# TeamB.net
KiCad netlist of a schematic drawn in EAGLE
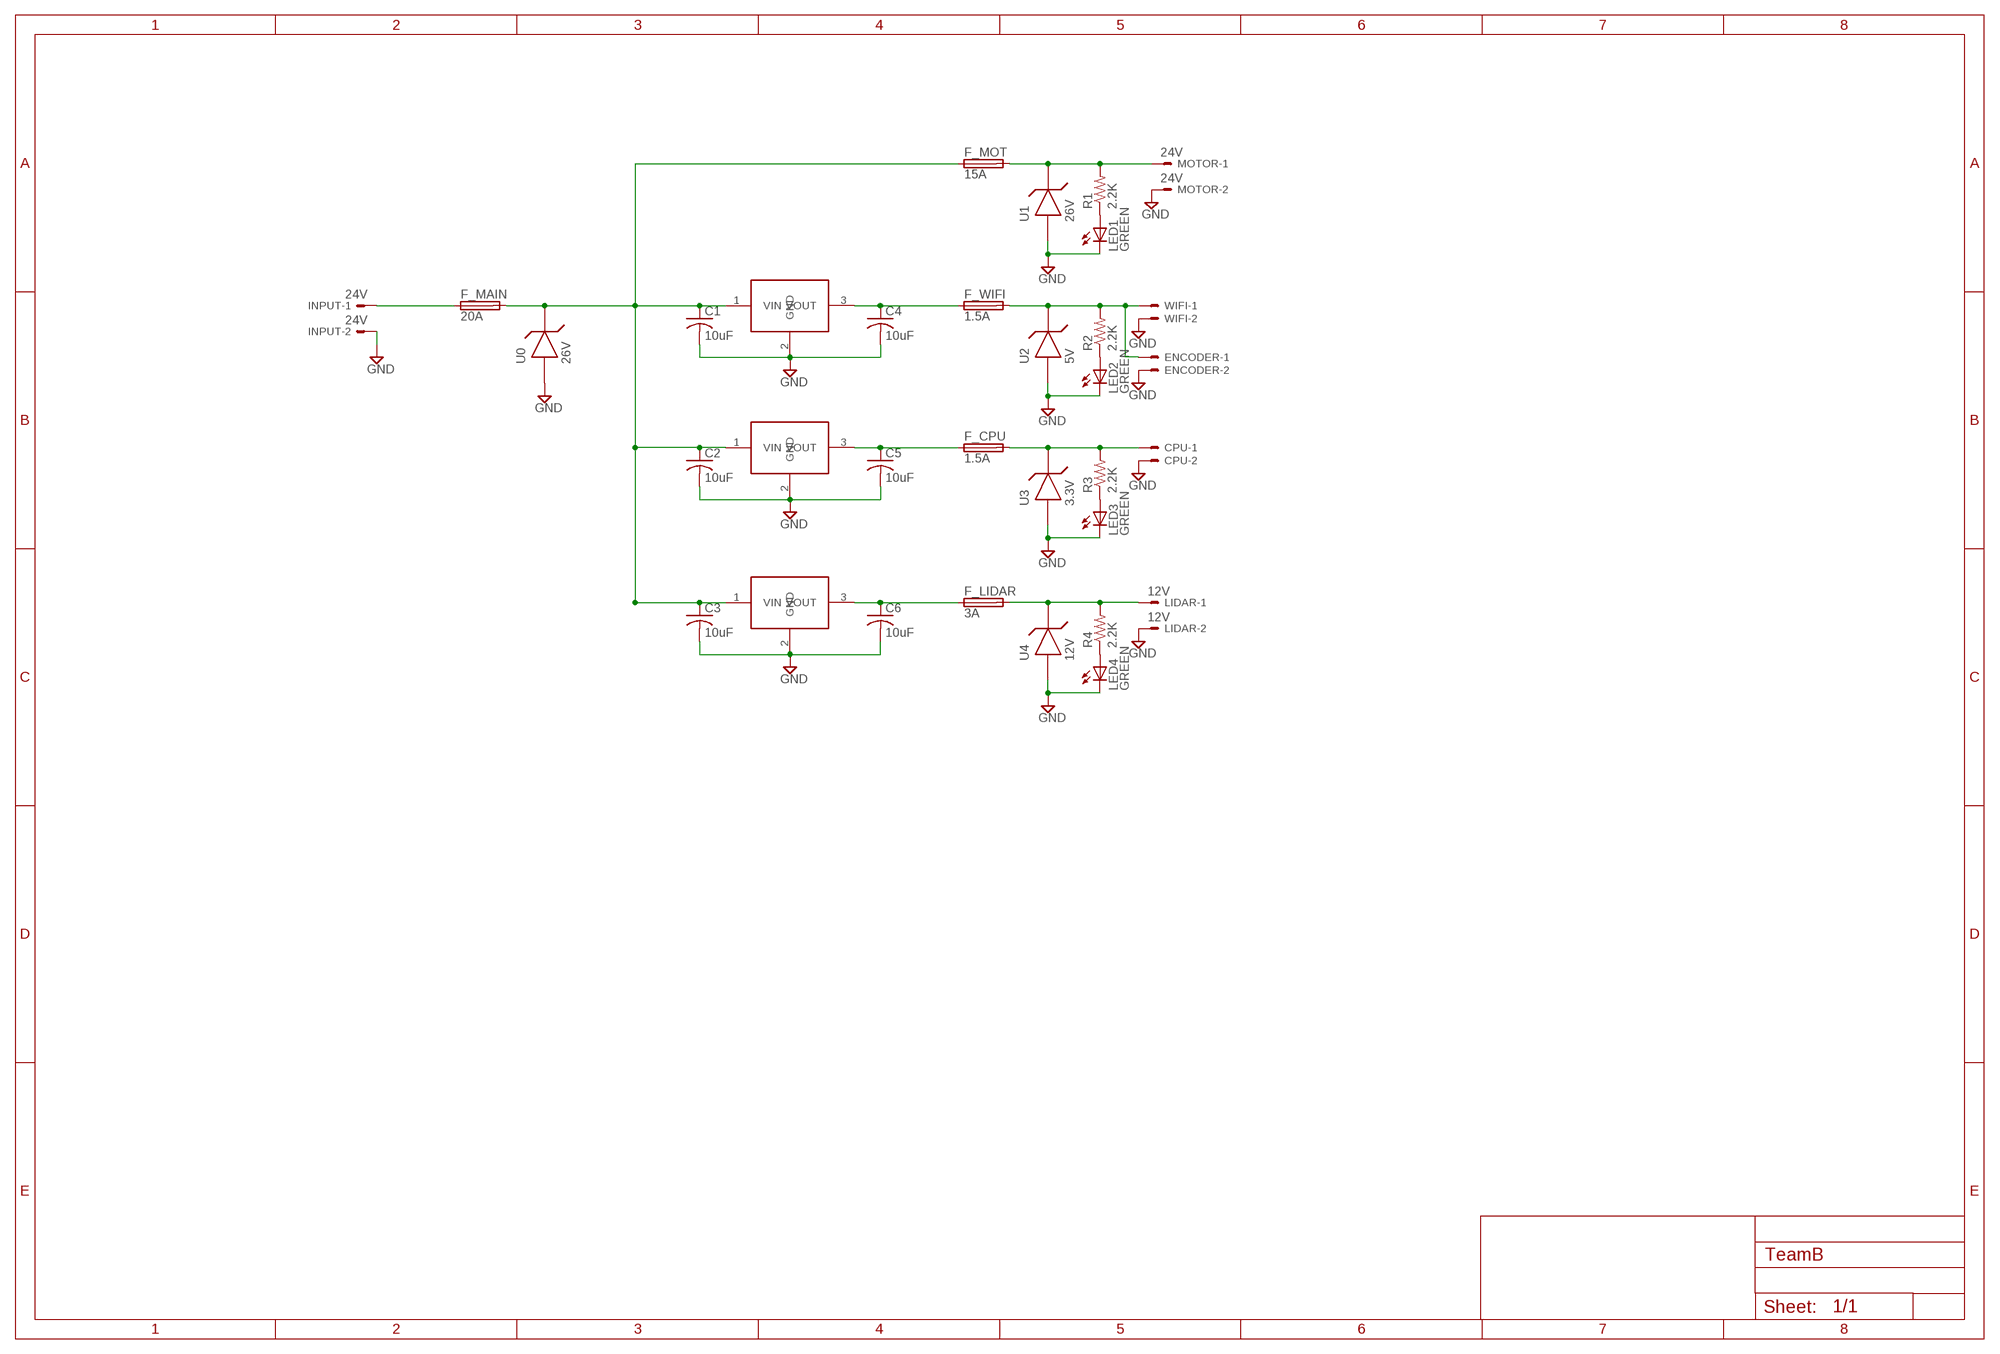
[diagram p0: schematic, sheet 1]

(export (version "E")
  (design (tool "Eeschema 10.0.6"))
  (components
    (comp (ref "C1")
      (value "10uF")
      (footprint "eagle-import:C1206")
      (libsource (lib "eagle-import") (part "C-USC1206"))
    )
    (comp (ref "C2")
      (value "10uF")
      (footprint "eagle-import:C1206")
      (libsource (lib "eagle-import") (part "C-USC1206"))
    )
    (comp (ref "C3")
      (value "10uF")
      (footprint "eagle-import:C1206")
      (libsource (lib "eagle-import") (part "C-USC1206"))
    )
    (comp (ref "C4")
      (value "10uF")
      (footprint "eagle-import:C1206")
      (libsource (lib "eagle-import") (part "C-USC1206"))
    )
    (comp (ref "C5")
      (value "10uF")
      (footprint "eagle-import:C1206")
      (libsource (lib "eagle-import") (part "C-USC1206"))
    )
    (comp (ref "C6")
      (value "10uF")
      (footprint "eagle-import:C1206")
      (libsource (lib "eagle-import") (part "C-USC1206"))
    )
    (comp (ref "CPU")
      (value "3.3V")
      (footprint "eagle-import:70553-02")
      (libsource (lib "eagle-import") (part "C-GRID-02-70553"))
    )
    (comp (ref "ENCODER")
      (value "5V")
      (footprint "eagle-import:70553-02")
      (libsource (lib "eagle-import") (part "C-GRID-02-70553"))
    )
    (comp (ref "F_CPU")
      (value "1.5A")
      (footprint "eagle-import:TE5")
      (libsource (lib "eagle-import") (part "TE5"))
    )
    (comp (ref "F_LIDAR")
      (value "3A")
      (footprint "eagle-import:TE5")
      (libsource (lib "eagle-import") (part "TE5"))
    )
    (comp (ref "F_MAIN")
      (value "20A")
      (footprint "eagle-import:TE5")
      (libsource (lib "eagle-import") (part "TE5"))
    )
    (comp (ref "F_MOT")
      (value "15A")
      (footprint "eagle-import:TE5")
      (libsource (lib "eagle-import") (part "TE5"))
    )
    (comp (ref "F_WIFI")
      (value "1.5A")
      (footprint "eagle-import:TE5")
      (libsource (lib "eagle-import") (part "TE5"))
    )
    (comp (ref "INPUT")
      (value "24V")
      (footprint "eagle-import:5566-2")
      (libsource (lib "eagle-import") (part "5566-2"))
    )
    (comp (ref "LED1")
      (value "GREEN")
      (footprint "eagle-import:SML1206")
      (libsource (lib "eagle-import") (part "LEDSML1206"))
    )
    (comp (ref "LED2")
      (value "GREEN")
      (footprint "eagle-import:SML1206")
      (libsource (lib "eagle-import") (part "LEDSML1206"))
    )
    (comp (ref "LED3")
      (value "GREEN")
      (footprint "eagle-import:SML1206")
      (libsource (lib "eagle-import") (part "LEDSML1206"))
    )
    (comp (ref "LED4")
      (value "GREEN")
      (footprint "eagle-import:SML1206")
      (libsource (lib "eagle-import") (part "LEDSML1206"))
    )
    (comp (ref "LIDAR")
      (value "12V")
      (footprint "eagle-import:5566-2")
      (libsource (lib "eagle-import") (part "5566-2"))
    )
    (comp (ref "MOTOR")
      (value "24V")
      (footprint "eagle-import:5566-2")
      (libsource (lib "eagle-import") (part "5566-2"))
    )
    (comp (ref "Q1")
      (value "MIC29300-5.0WU")
      (footprint "eagle-import:TO220")
      (libsource (lib "eagle-import") (part "MIC29150/29300/29500"))
    )
    (comp (ref "Q2")
      (value "MIC29300-3.3WU")
      (footprint "eagle-import:TO220")
      (libsource (lib "eagle-import") (part "MIC29150/29300/29500"))
    )
    (comp (ref "Q3")
      (value "MIC29300-12WU")
      (footprint "eagle-import:TO220")
      (libsource (lib "eagle-import") (part "MIC29150/29300/29500"))
    )
    (comp (ref "R1")
      (value "2.2K")
      (footprint "eagle-import:R1206")
      (libsource (lib "eagle-import") (part "R-US_R1206"))
    )
    (comp (ref "R2")
      (value "2.2K")
      (footprint "eagle-import:R1206")
      (libsource (lib "eagle-import") (part "R-US_R1206"))
    )
    (comp (ref "R3")
      (value "2.2K")
      (footprint "eagle-import:R1206")
      (libsource (lib "eagle-import") (part "R-US_R1206"))
    )
    (comp (ref "R4")
      (value "2.2K")
      (footprint "eagle-import:R1206")
      (libsource (lib "eagle-import") (part "R-US_R1206"))
    )
    (comp (ref "U0")
      (value "26V")
      (footprint "eagle-import:SMA")
      (libsource (lib "eagle-import") (part "TVS-DIODE-SMA"))
    )
    (comp (ref "U1")
      (value "26V")
      (footprint "eagle-import:SMA")
      (libsource (lib "eagle-import") (part "TVS-DIODE-SMA"))
    )
    (comp (ref "U2")
      (value "5V")
      (footprint "eagle-import:SMA")
      (libsource (lib "eagle-import") (part "TVS-DIODE-SMA"))
    )
    (comp (ref "U3")
      (value "3.3V")
      (footprint "eagle-import:SMB")
      (libsource (lib "eagle-import") (part "TVS-DIODE-SMB"))
    )
    (comp (ref "U4")
      (value "12V")
      (footprint "eagle-import:SMA")
      (libsource (lib "eagle-import") (part "TVS-DIODE-SMA"))
    )
    (comp (ref "WIFI")
      (value "5V")
      (footprint "eagle-import:70553-02")
      (libsource (lib "eagle-import") (part "C-GRID-02-70553"))
    )
  )
  (nets
    (net (code "1") (name "GND") (class "Default")
      (node (ref "C1") (pin "2") (pinfunction "2_2") (pintype "passive"))
      (node (ref "C2") (pin "2") (pinfunction "2_2") (pintype "passive"))
      (node (ref "C3") (pin "2") (pinfunction "2_2") (pintype "passive"))
      (node (ref "C4") (pin "2") (pinfunction "2_2") (pintype "passive"))
      (node (ref "C5") (pin "2") (pinfunction "2_2") (pintype "passive"))
      (node (ref "C6") (pin "2") (pinfunction "2_2") (pintype "passive"))
      (node (ref "CPU") (pin "2") (pinfunction "S_2") (pintype "passive"))
      (node (ref "ENCODER") (pin "2") (pinfunction "S_2") (pintype "passive"))
      (node (ref "INPUT") (pin "2") (pinfunction "S_2") (pintype "passive"))
      (node (ref "LED1") (pin "C") (pinfunction "C_C") (pintype "passive"))
      (node (ref "LED2") (pin "C") (pinfunction "C_C") (pintype "passive"))
      (node (ref "LED3") (pin "C") (pinfunction "C_C") (pintype "passive"))
      (node (ref "LED4") (pin "C") (pinfunction "C_C") (pintype "passive"))
      (node (ref "LIDAR") (pin "2") (pinfunction "S_2") (pintype "passive"))
      (node (ref "MOTOR") (pin "2") (pinfunction "S_2") (pintype "passive"))
      (node (ref "Q1") (pin "2") (pinfunction "GND_2") (pintype "bidirectional"))
      (node (ref "Q2") (pin "2") (pinfunction "GND_2") (pintype "bidirectional"))
      (node (ref "Q3") (pin "2") (pinfunction "GND_2") (pintype "bidirectional"))
      (node (ref "U0") (pin "AN") (pinfunction "AN_AN") (pintype "bidirectional"))
      (node (ref "U1") (pin "AN") (pinfunction "AN_AN") (pintype "bidirectional"))
      (node (ref "U2") (pin "AN") (pinfunction "AN_AN") (pintype "bidirectional"))
      (node (ref "U3") (pin "AN") (pinfunction "AN_AN") (pintype "bidirectional"))
      (node (ref "U4") (pin "AN") (pinfunction "AN_AN") (pintype "bidirectional"))
      (node (ref "WIFI") (pin "2") (pinfunction "S_2") (pintype "passive"))
    )
    (net (code "2") (name "Net-(CPUA-S)") (class "Default")
      (node (ref "CPU") (pin "1") (pinfunction "S_1") (pintype "passive"))
      (node (ref "F_CPU") (pin "2") (pinfunction "2_2") (pintype "passive"))
      (node (ref "R3") (pin "2") (pinfunction "2_2") (pintype "passive"))
      (node (ref "U3") (pin "CAT") (pinfunction "CAT_CAT") (pintype "bidirectional"))
    )
    (net (code "3") (name "Net-(ENCODERA-S)") (class "Default")
      (node (ref "ENCODER") (pin "1") (pinfunction "S_1") (pintype "passive"))
      (node (ref "F_WIFI") (pin "2") (pinfunction "2_2") (pintype "passive"))
      (node (ref "R2") (pin "2") (pinfunction "2_2") (pintype "passive"))
      (node (ref "U2") (pin "CAT") (pinfunction "CAT_CAT") (pintype "bidirectional"))
      (node (ref "WIFI") (pin "1") (pinfunction "S_1") (pintype "passive"))
    )
    (net (code "4") (name "Net-(INPUTA-S)") (class "Default")
      (node (ref "F_MAIN") (pin "1") (pinfunction "1_1") (pintype "passive"))
      (node (ref "INPUT") (pin "1") (pinfunction "S_1") (pintype "passive"))
    )
    (net (code "5") (name "Net-(LED1-PadA)") (class "Default")
      (node (ref "LED1") (pin "A") (pinfunction "A_A") (pintype "passive"))
      (node (ref "R1") (pin "1") (pinfunction "1_1") (pintype "passive"))
    )
    (net (code "6") (name "Net-(LED2-PadA)") (class "Default")
      (node (ref "LED2") (pin "A") (pinfunction "A_A") (pintype "passive"))
      (node (ref "R2") (pin "1") (pinfunction "1_1") (pintype "passive"))
    )
    (net (code "7") (name "Net-(LED3-PadA)") (class "Default")
      (node (ref "LED3") (pin "A") (pinfunction "A_A") (pintype "passive"))
      (node (ref "R3") (pin "1") (pinfunction "1_1") (pintype "passive"))
    )
    (net (code "8") (name "Net-(LED4-PadA)") (class "Default")
      (node (ref "LED4") (pin "A") (pinfunction "A_A") (pintype "passive"))
      (node (ref "R4") (pin "1") (pinfunction "1_1") (pintype "passive"))
    )
    (net (code "9") (name "Net-(LIDARA-S)") (class "Default")
      (node (ref "F_LIDAR") (pin "2") (pinfunction "2_2") (pintype "passive"))
      (node (ref "LIDAR") (pin "1") (pinfunction "S_1") (pintype "passive"))
      (node (ref "R4") (pin "2") (pinfunction "2_2") (pintype "passive"))
      (node (ref "U4") (pin "CAT") (pinfunction "CAT_CAT") (pintype "bidirectional"))
    )
    (net (code "10") (name "Net-(MOTORA-S)") (class "Default")
      (node (ref "F_MOT") (pin "2") (pinfunction "2_2") (pintype "passive"))
      (node (ref "MOTOR") (pin "1") (pinfunction "S_1") (pintype "passive"))
      (node (ref "R1") (pin "2") (pinfunction "2_2") (pintype "passive"))
      (node (ref "U1") (pin "CAT") (pinfunction "CAT_CAT") (pintype "bidirectional"))
    )
    (net (code "11") (name "Net-(Q1-VIN)") (class "Default")
      (node (ref "C1") (pin "1") (pinfunction "1_1") (pintype "passive"))
      (node (ref "C2") (pin "1") (pinfunction "1_1") (pintype "passive"))
      (node (ref "C3") (pin "1") (pinfunction "1_1") (pintype "passive"))
      (node (ref "F_MAIN") (pin "2") (pinfunction "2_2") (pintype "passive"))
      (node (ref "F_MOT") (pin "1") (pinfunction "1_1") (pintype "passive"))
      (node (ref "Q1") (pin "1") (pinfunction "VIN_1") (pintype "bidirectional"))
      (node (ref "Q2") (pin "1") (pinfunction "VIN_1") (pintype "bidirectional"))
      (node (ref "Q3") (pin "1") (pinfunction "VIN_1") (pintype "bidirectional"))
      (node (ref "U0") (pin "CAT") (pinfunction "CAT_CAT") (pintype "bidirectional"))
    )
    (net (code "12") (name "Net-(Q1-VOUT)") (class "Default")
      (node (ref "C4") (pin "1") (pinfunction "1_1") (pintype "passive"))
      (node (ref "F_WIFI") (pin "1") (pinfunction "1_1") (pintype "passive"))
      (node (ref "Q1") (pin "3") (pinfunction "VOUT_3") (pintype "bidirectional"))
    )
    (net (code "13") (name "Net-(Q2-VOUT)") (class "Default")
      (node (ref "C5") (pin "1") (pinfunction "1_1") (pintype "passive"))
      (node (ref "F_CPU") (pin "1") (pinfunction "1_1") (pintype "passive"))
      (node (ref "Q2") (pin "3") (pinfunction "VOUT_3") (pintype "bidirectional"))
    )
    (net (code "14") (name "Net-(Q3-VOUT)") (class "Default")
      (node (ref "C6") (pin "1") (pinfunction "1_1") (pintype "passive"))
      (node (ref "F_LIDAR") (pin "1") (pinfunction "1_1") (pintype "passive"))
      (node (ref "Q3") (pin "3") (pinfunction "VOUT_3") (pintype "bidirectional"))
    )
  )
)
